# my-forecast.net
KiCad netlist of a schematic drawn in EAGLE
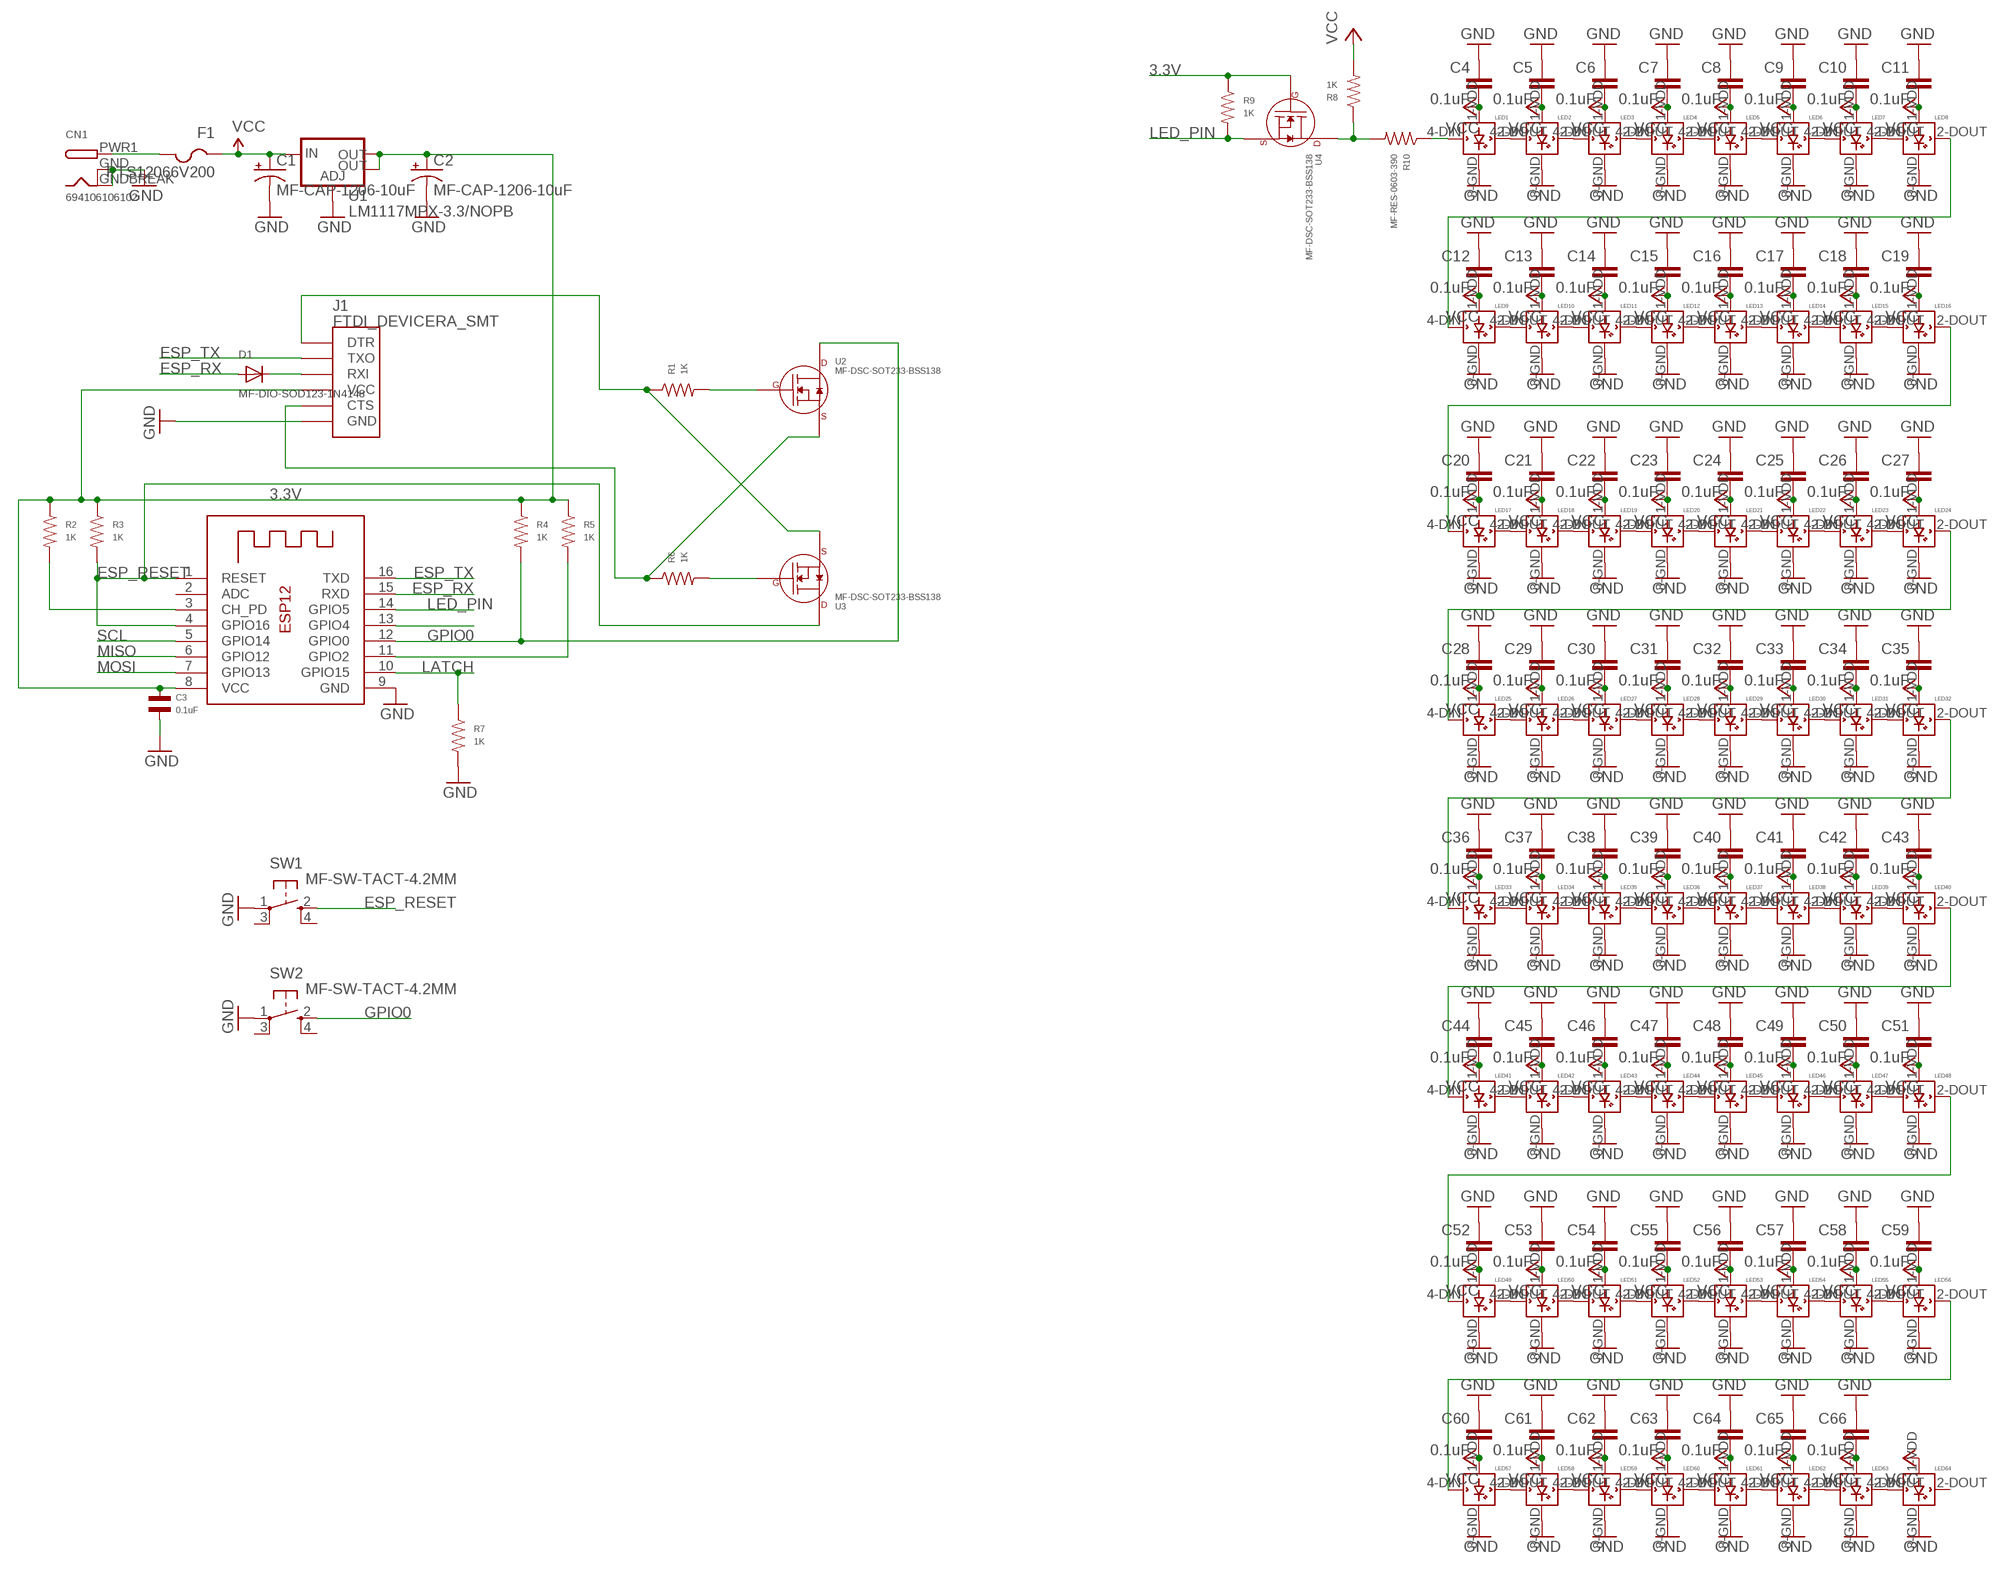
[diagram p0: schematic, sheet 1]

(export (version "E")
  (design (tool "Eeschema 10.0.6"))
  (components
    (comp (ref "C1")
      (value "MF-CAP-1206-10uF")
      (footprint "eagle-import:EIA3216")
      (libsource (lib "eagle-import") (part "CAP_POL1206"))
    )
    (comp (ref "C2")
      (value "MF-CAP-1206-10uF")
      (footprint "eagle-import:EIA3216")
      (libsource (lib "eagle-import") (part "CAP_POL1206"))
    )
    (comp (ref "C3")
      (value "0.1uF")
      (footprint "eagle-import:C0603")
      (libsource (lib "eagle-import") (part "CAPACITOR_NP_0603"))
    )
    (comp (ref "C4")
      (value "0.1uF")
      (footprint "eagle-import:0603-CAP")
      (libsource (lib "eagle-import") (part "CAP0603-CAP"))
    )
    (comp (ref "C5")
      (value "0.1uF")
      (footprint "eagle-import:0603-CAP")
      (libsource (lib "eagle-import") (part "CAP0603-CAP"))
    )
    (comp (ref "C6")
      (value "0.1uF")
      (footprint "eagle-import:0603-CAP")
      (libsource (lib "eagle-import") (part "CAP0603-CAP"))
    )
    (comp (ref "C7")
      (value "0.1uF")
      (footprint "eagle-import:0603-CAP")
      (libsource (lib "eagle-import") (part "CAP0603-CAP"))
    )
    (comp (ref "C8")
      (value "0.1uF")
      (footprint "eagle-import:0603-CAP")
      (libsource (lib "eagle-import") (part "CAP0603-CAP"))
    )
    (comp (ref "C9")
      (value "0.1uF")
      (footprint "eagle-import:0603-CAP")
      (libsource (lib "eagle-import") (part "CAP0603-CAP"))
    )
    (comp (ref "C10")
      (value "0.1uF")
      (footprint "eagle-import:0603-CAP")
      (libsource (lib "eagle-import") (part "CAP0603-CAP"))
    )
    (comp (ref "C11")
      (value "0.1uF")
      (footprint "eagle-import:0603-CAP")
      (libsource (lib "eagle-import") (part "CAP0603-CAP"))
    )
    (comp (ref "C12")
      (value "0.1uF")
      (footprint "eagle-import:0603-CAP")
      (libsource (lib "eagle-import") (part "CAP0603-CAP"))
    )
    (comp (ref "C13")
      (value "0.1uF")
      (footprint "eagle-import:0603-CAP")
      (libsource (lib "eagle-import") (part "CAP0603-CAP"))
    )
    (comp (ref "C14")
      (value "0.1uF")
      (footprint "eagle-import:0603-CAP")
      (libsource (lib "eagle-import") (part "CAP0603-CAP"))
    )
    (comp (ref "C15")
      (value "0.1uF")
      (footprint "eagle-import:0603-CAP")
      (libsource (lib "eagle-import") (part "CAP0603-CAP"))
    )
    (comp (ref "C16")
      (value "0.1uF")
      (footprint "eagle-import:0603-CAP")
      (libsource (lib "eagle-import") (part "CAP0603-CAP"))
    )
    (comp (ref "C17")
      (value "0.1uF")
      (footprint "eagle-import:0603-CAP")
      (libsource (lib "eagle-import") (part "CAP0603-CAP"))
    )
    (comp (ref "C18")
      (value "0.1uF")
      (footprint "eagle-import:0603-CAP")
      (libsource (lib "eagle-import") (part "CAP0603-CAP"))
    )
    (comp (ref "C19")
      (value "0.1uF")
      (footprint "eagle-import:0603-CAP")
      (libsource (lib "eagle-import") (part "CAP0603-CAP"))
    )
    (comp (ref "C20")
      (value "0.1uF")
      (footprint "eagle-import:0603-CAP")
      (libsource (lib "eagle-import") (part "CAP0603-CAP"))
    )
    (comp (ref "C21")
      (value "0.1uF")
      (footprint "eagle-import:0603-CAP")
      (libsource (lib "eagle-import") (part "CAP0603-CAP"))
    )
    (comp (ref "C22")
      (value "0.1uF")
      (footprint "eagle-import:0603-CAP")
      (libsource (lib "eagle-import") (part "CAP0603-CAP"))
    )
    (comp (ref "C23")
      (value "0.1uF")
      (footprint "eagle-import:0603-CAP")
      (libsource (lib "eagle-import") (part "CAP0603-CAP"))
    )
    (comp (ref "C24")
      (value "0.1uF")
      (footprint "eagle-import:0603-CAP")
      (libsource (lib "eagle-import") (part "CAP0603-CAP"))
    )
    (comp (ref "C25")
      (value "0.1uF")
      (footprint "eagle-import:0603-CAP")
      (libsource (lib "eagle-import") (part "CAP0603-CAP"))
    )
    (comp (ref "C26")
      (value "0.1uF")
      (footprint "eagle-import:0603-CAP")
      (libsource (lib "eagle-import") (part "CAP0603-CAP"))
    )
    (comp (ref "C27")
      (value "0.1uF")
      (footprint "eagle-import:0603-CAP")
      (libsource (lib "eagle-import") (part "CAP0603-CAP"))
    )
    (comp (ref "C28")
      (value "0.1uF")
      (footprint "eagle-import:0603-CAP")
      (libsource (lib "eagle-import") (part "CAP0603-CAP"))
    )
    (comp (ref "C29")
      (value "0.1uF")
      (footprint "eagle-import:0603-CAP")
      (libsource (lib "eagle-import") (part "CAP0603-CAP"))
    )
    (comp (ref "C30")
      (value "0.1uF")
      (footprint "eagle-import:0603-CAP")
      (libsource (lib "eagle-import") (part "CAP0603-CAP"))
    )
    (comp (ref "C31")
      (value "0.1uF")
      (footprint "eagle-import:0603-CAP")
      (libsource (lib "eagle-import") (part "CAP0603-CAP"))
    )
    (comp (ref "C32")
      (value "0.1uF")
      (footprint "eagle-import:0603-CAP")
      (libsource (lib "eagle-import") (part "CAP0603-CAP"))
    )
    (comp (ref "C33")
      (value "0.1uF")
      (footprint "eagle-import:0603-CAP")
      (libsource (lib "eagle-import") (part "CAP0603-CAP"))
    )
    (comp (ref "C34")
      (value "0.1uF")
      (footprint "eagle-import:0603-CAP")
      (libsource (lib "eagle-import") (part "CAP0603-CAP"))
    )
    (comp (ref "C35")
      (value "0.1uF")
      (footprint "eagle-import:0603-CAP")
      (libsource (lib "eagle-import") (part "CAP0603-CAP"))
    )
    (comp (ref "C36")
      (value "0.1uF")
      (footprint "eagle-import:0603-CAP")
      (libsource (lib "eagle-import") (part "CAP0603-CAP"))
    )
    (comp (ref "C37")
      (value "0.1uF")
      (footprint "eagle-import:0603-CAP")
      (libsource (lib "eagle-import") (part "CAP0603-CAP"))
    )
    (comp (ref "C38")
      (value "0.1uF")
      (footprint "eagle-import:0603-CAP")
      (libsource (lib "eagle-import") (part "CAP0603-CAP"))
    )
    (comp (ref "C39")
      (value "0.1uF")
      (footprint "eagle-import:0603-CAP")
      (libsource (lib "eagle-import") (part "CAP0603-CAP"))
    )
    (comp (ref "C40")
      (value "0.1uF")
      (footprint "eagle-import:0603-CAP")
      (libsource (lib "eagle-import") (part "CAP0603-CAP"))
    )
    (comp (ref "C41")
      (value "0.1uF")
      (footprint "eagle-import:0603-CAP")
      (libsource (lib "eagle-import") (part "CAP0603-CAP"))
    )
    (comp (ref "C42")
      (value "0.1uF")
      (footprint "eagle-import:0603-CAP")
      (libsource (lib "eagle-import") (part "CAP0603-CAP"))
    )
    (comp (ref "C43")
      (value "0.1uF")
      (footprint "eagle-import:0603-CAP")
      (libsource (lib "eagle-import") (part "CAP0603-CAP"))
    )
    (comp (ref "C44")
      (value "0.1uF")
      (footprint "eagle-import:0603-CAP")
      (libsource (lib "eagle-import") (part "CAP0603-CAP"))
    )
    (comp (ref "C45")
      (value "0.1uF")
      (footprint "eagle-import:0603-CAP")
      (libsource (lib "eagle-import") (part "CAP0603-CAP"))
    )
    (comp (ref "C46")
      (value "0.1uF")
      (footprint "eagle-import:0603-CAP")
      (libsource (lib "eagle-import") (part "CAP0603-CAP"))
    )
    (comp (ref "C47")
      (value "0.1uF")
      (footprint "eagle-import:0603-CAP")
      (libsource (lib "eagle-import") (part "CAP0603-CAP"))
    )
    (comp (ref "C48")
      (value "0.1uF")
      (footprint "eagle-import:0603-CAP")
      (libsource (lib "eagle-import") (part "CAP0603-CAP"))
    )
    (comp (ref "C49")
      (value "0.1uF")
      (footprint "eagle-import:0603-CAP")
      (libsource (lib "eagle-import") (part "CAP0603-CAP"))
    )
    (comp (ref "C50")
      (value "0.1uF")
      (footprint "eagle-import:0603-CAP")
      (libsource (lib "eagle-import") (part "CAP0603-CAP"))
    )
    (comp (ref "C51")
      (value "0.1uF")
      (footprint "eagle-import:0603-CAP")
      (libsource (lib "eagle-import") (part "CAP0603-CAP"))
    )
    (comp (ref "C52")
      (value "0.1uF")
      (footprint "eagle-import:0603-CAP")
      (libsource (lib "eagle-import") (part "CAP0603-CAP"))
    )
    (comp (ref "C53")
      (value "0.1uF")
      (footprint "eagle-import:0603-CAP")
      (libsource (lib "eagle-import") (part "CAP0603-CAP"))
    )
    (comp (ref "C54")
      (value "0.1uF")
      (footprint "eagle-import:0603-CAP")
      (libsource (lib "eagle-import") (part "CAP0603-CAP"))
    )
    (comp (ref "C55")
      (value "0.1uF")
      (footprint "eagle-import:0603-CAP")
      (libsource (lib "eagle-import") (part "CAP0603-CAP"))
    )
    (comp (ref "C56")
      (value "0.1uF")
      (footprint "eagle-import:0603-CAP")
      (libsource (lib "eagle-import") (part "CAP0603-CAP"))
    )
    (comp (ref "C57")
      (value "0.1uF")
      (footprint "eagle-import:0603-CAP")
      (libsource (lib "eagle-import") (part "CAP0603-CAP"))
    )
    (comp (ref "C58")
      (value "0.1uF")
      (footprint "eagle-import:0603-CAP")
      (libsource (lib "eagle-import") (part "CAP0603-CAP"))
    )
    (comp (ref "C59")
      (value "0.1uF")
      (footprint "eagle-import:0603-CAP")
      (libsource (lib "eagle-import") (part "CAP0603-CAP"))
    )
    (comp (ref "C60")
      (value "0.1uF")
      (footprint "eagle-import:0603-CAP")
      (libsource (lib "eagle-import") (part "CAP0603-CAP"))
    )
    (comp (ref "C61")
      (value "0.1uF")
      (footprint "eagle-import:0603-CAP")
      (libsource (lib "eagle-import") (part "CAP0603-CAP"))
    )
    (comp (ref "C62")
      (value "0.1uF")
      (footprint "eagle-import:0603-CAP")
      (libsource (lib "eagle-import") (part "CAP0603-CAP"))
    )
    (comp (ref "C63")
      (value "0.1uF")
      (footprint "eagle-import:0603-CAP")
      (libsource (lib "eagle-import") (part "CAP0603-CAP"))
    )
    (comp (ref "C64")
      (value "0.1uF")
      (footprint "eagle-import:0603-CAP")
      (libsource (lib "eagle-import") (part "CAP0603-CAP"))
    )
    (comp (ref "C65")
      (value "0.1uF")
      (footprint "eagle-import:0603-CAP")
      (libsource (lib "eagle-import") (part "CAP0603-CAP"))
    )
    (comp (ref "C66")
      (value "0.1uF")
      (footprint "eagle-import:0603-CAP")
      (libsource (lib "eagle-import") (part "CAP0603-CAP"))
    )
    (comp (ref "CN1")
      (value "694106106102")
      (footprint "eagle-import:DCJACK_2MM_SMT")
      (libsource (lib "eagle-import") (part "DCBARRELSMT"))
    )
    (comp (ref "D1")
      (value "MF-DIO-SOD123-1N4148")
      (footprint "eagle-import:SOD-123")
      (libsource (lib "eagle-import") (part "DIODESOD-123"))
    )
    (comp (ref "F1")
      (value "PTS12066V200")
      (footprint "eagle-import:R1206")
      (libsource (lib "eagle-import") (part "PTCFUSE-1206"))
    )
    (comp (ref "J1")
      (value "FTDI_DEVICERA_SMT")
      (footprint "eagle-import:FTDI_DEVICE_RA_SMT")
      (libsource (lib "eagle-import") (part "FTDI_DEVICERA_SMT"))
    )
    (comp (ref "LED1")
      (value "WS2812B5050")
      (footprint "eagle-import:WS2812B")
      (libsource (lib "eagle-import") (part "WS2812B5050"))
    )
    (comp (ref "LED2")
      (value "WS2812B5050")
      (footprint "eagle-import:WS2812B")
      (libsource (lib "eagle-import") (part "WS2812B5050"))
    )
    (comp (ref "LED3")
      (value "WS2812B5050")
      (footprint "eagle-import:WS2812B")
      (libsource (lib "eagle-import") (part "WS2812B5050"))
    )
    (comp (ref "LED4")
      (value "WS2812B5050")
      (footprint "eagle-import:WS2812B")
      (libsource (lib "eagle-import") (part "WS2812B5050"))
    )
    (comp (ref "LED5")
      (value "WS2812B5050")
      (footprint "eagle-import:WS2812B")
      (libsource (lib "eagle-import") (part "WS2812B5050"))
    )
    (comp (ref "LED6")
      (value "WS2812B5050")
      (footprint "eagle-import:WS2812B")
      (libsource (lib "eagle-import") (part "WS2812B5050"))
    )
    (comp (ref "LED7")
      (value "WS2812B5050")
      (footprint "eagle-import:WS2812B")
      (libsource (lib "eagle-import") (part "WS2812B5050"))
    )
    (comp (ref "LED8")
      (value "WS2812B5050")
      (footprint "eagle-import:WS2812B")
      (libsource (lib "eagle-import") (part "WS2812B5050"))
    )
    (comp (ref "LED9")
      (value "WS2812B5050")
      (footprint "eagle-import:WS2812B")
      (libsource (lib "eagle-import") (part "WS2812B5050"))
    )
    (comp (ref "LED10")
      (value "WS2812B5050")
      (footprint "eagle-import:WS2812B")
      (libsource (lib "eagle-import") (part "WS2812B5050"))
    )
    (comp (ref "LED11")
      (value "WS2812B5050")
      (footprint "eagle-import:WS2812B")
      (libsource (lib "eagle-import") (part "WS2812B5050"))
    )
    (comp (ref "LED12")
      (value "WS2812B5050")
      (footprint "eagle-import:WS2812B")
      (libsource (lib "eagle-import") (part "WS2812B5050"))
    )
    (comp (ref "LED13")
      (value "WS2812B5050")
      (footprint "eagle-import:WS2812B")
      (libsource (lib "eagle-import") (part "WS2812B5050"))
    )
    (comp (ref "LED14")
      (value "WS2812B5050")
      (footprint "eagle-import:WS2812B")
      (libsource (lib "eagle-import") (part "WS2812B5050"))
    )
    (comp (ref "LED15")
      (value "WS2812B5050")
      (footprint "eagle-import:WS2812B")
      (libsource (lib "eagle-import") (part "WS2812B5050"))
    )
    (comp (ref "LED16")
      (value "WS2812B5050")
      (footprint "eagle-import:WS2812B")
      (libsource (lib "eagle-import") (part "WS2812B5050"))
    )
    (comp (ref "LED17")
      (value "WS2812B5050")
      (footprint "eagle-import:WS2812B")
      (libsource (lib "eagle-import") (part "WS2812B5050"))
    )
    (comp (ref "LED18")
      (value "WS2812B5050")
      (footprint "eagle-import:WS2812B")
      (libsource (lib "eagle-import") (part "WS2812B5050"))
    )
    (comp (ref "LED19")
      (value "WS2812B5050")
      (footprint "eagle-import:WS2812B")
      (libsource (lib "eagle-import") (part "WS2812B5050"))
    )
    (comp (ref "LED20")
      (value "WS2812B5050")
      (footprint "eagle-import:WS2812B")
      (libsource (lib "eagle-import") (part "WS2812B5050"))
    )
    (comp (ref "LED21")
      (value "WS2812B5050")
      (footprint "eagle-import:WS2812B")
      (libsource (lib "eagle-import") (part "WS2812B5050"))
    )
    (comp (ref "LED22")
      (value "WS2812B5050")
      (footprint "eagle-import:WS2812B")
      (libsource (lib "eagle-import") (part "WS2812B5050"))
    )
    (comp (ref "LED23")
      (value "WS2812B5050")
      (footprint "eagle-import:WS2812B")
      (libsource (lib "eagle-import") (part "WS2812B5050"))
    )
    (comp (ref "LED24")
      (value "WS2812B5050")
      (footprint "eagle-import:WS2812B")
      (libsource (lib "eagle-import") (part "WS2812B5050"))
    )
    (comp (ref "LED25")
      (value "WS2812B5050")
      (footprint "eagle-import:WS2812B")
      (libsource (lib "eagle-import") (part "WS2812B5050"))
    )
    (comp (ref "LED26")
      (value "WS2812B5050")
      (footprint "eagle-import:WS2812B")
      (libsource (lib "eagle-import") (part "WS2812B5050"))
    )
    (comp (ref "LED27")
      (value "WS2812B5050")
      (footprint "eagle-import:WS2812B")
      (libsource (lib "eagle-import") (part "WS2812B5050"))
    )
    (comp (ref "LED28")
      (value "WS2812B5050")
      (footprint "eagle-import:WS2812B")
      (libsource (lib "eagle-import") (part "WS2812B5050"))
    )
    (comp (ref "LED29")
      (value "WS2812B5050")
      (footprint "eagle-import:WS2812B")
      (libsource (lib "eagle-import") (part "WS2812B5050"))
    )
    (comp (ref "LED30")
      (value "WS2812B5050")
      (footprint "eagle-import:WS2812B")
      (libsource (lib "eagle-import") (part "WS2812B5050"))
    )
    (comp (ref "LED31")
      (value "WS2812B5050")
      (footprint "eagle-import:WS2812B")
      (libsource (lib "eagle-import") (part "WS2812B5050"))
    )
    (comp (ref "LED32")
      (value "WS2812B5050")
      (footprint "eagle-import:WS2812B")
      (libsource (lib "eagle-import") (part "WS2812B5050"))
    )
    (comp (ref "LED33")
      (value "WS2812B5050")
      (footprint "eagle-import:WS2812B")
      (libsource (lib "eagle-import") (part "WS2812B5050"))
    )
    (comp (ref "LED34")
      (value "WS2812B5050")
      (footprint "eagle-import:WS2812B")
      (libsource (lib "eagle-import") (part "WS2812B5050"))
    )
    (comp (ref "LED35")
      (value "WS2812B5050")
      (footprint "eagle-import:WS2812B")
      (libsource (lib "eagle-import") (part "WS2812B5050"))
    )
    (comp (ref "LED36")
      (value "WS2812B5050")
      (footprint "eagle-import:WS2812B")
      (libsource (lib "eagle-import") (part "WS2812B5050"))
    )
    (comp (ref "LED37")
      (value "WS2812B5050")
      (footprint "eagle-import:WS2812B")
      (libsource (lib "eagle-import") (part "WS2812B5050"))
    )
    (comp (ref "LED38")
      (value "WS2812B5050")
      (footprint "eagle-import:WS2812B")
      (libsource (lib "eagle-import") (part "WS2812B5050"))
    )
    (comp (ref "LED39")
      (value "WS2812B5050")
      (footprint "eagle-import:WS2812B")
      (libsource (lib "eagle-import") (part "WS2812B5050"))
    )
    (comp (ref "LED40")
      (value "WS2812B5050")
      (footprint "eagle-import:WS2812B")
      (libsource (lib "eagle-import") (part "WS2812B5050"))
    )
    (comp (ref "LED41")
      (value "WS2812B5050")
      (footprint "eagle-import:WS2812B")
      (libsource (lib "eagle-import") (part "WS2812B5050"))
    )
    (comp (ref "LED42")
      (value "WS2812B5050")
      (footprint "eagle-import:WS2812B")
      (libsource (lib "eagle-import") (part "WS2812B5050"))
    )
    (comp (ref "LED43")
      (value "WS2812B5050")
      (footprint "eagle-import:WS2812B")
      (libsource (lib "eagle-import") (part "WS2812B5050"))
    )
    (comp (ref "LED44")
      (value "WS2812B5050")
      (footprint "eagle-import:WS2812B")
      (libsource (lib "eagle-import") (part "WS2812B5050"))
    )
    (comp (ref "LED45")
      (value "WS2812B5050")
      (footprint "eagle-import:WS2812B")
      (libsource (lib "eagle-import") (part "WS2812B5050"))
    )
    (comp (ref "LED46")
      (value "WS2812B5050")
      (footprint "eagle-import:WS2812B")
      (libsource (lib "eagle-import") (part "WS2812B5050"))
    )
    (comp (ref "LED47")
      (value "WS2812B5050")
      (footprint "eagle-import:WS2812B")
      (libsource (lib "eagle-import") (part "WS2812B5050"))
    )
    (comp (ref "LED48")
      (value "WS2812B5050")
      (footprint "eagle-import:WS2812B")
      (libsource (lib "eagle-import") (part "WS2812B5050"))
    )
    (comp (ref "LED49")
      (value "WS2812B5050")
      (footprint "eagle-import:WS2812B")
      (libsource (lib "eagle-import") (part "WS2812B5050"))
    )
    (comp (ref "LED50")
      (value "WS2812B5050")
      (footprint "eagle-import:WS2812B")
      (libsource (lib "eagle-import") (part "WS2812B5050"))
    )
    (comp (ref "LED51")
      (value "WS2812B5050")
      (footprint "eagle-import:WS2812B")
      (libsource (lib "eagle-import") (part "WS2812B5050"))
    )
    (comp (ref "LED52")
      (value "WS2812B5050")
      (footprint "eagle-import:WS2812B")
      (libsource (lib "eagle-import") (part "WS2812B5050"))
    )
    (comp (ref "LED53")
      (value "WS2812B5050")
      (footprint "eagle-import:WS2812B")
      (libsource (lib "eagle-import") (part "WS2812B5050"))
    )
    (comp (ref "LED54")
      (value "WS2812B5050")
      (footprint "eagle-import:WS2812B")
      (libsource (lib "eagle-import") (part "WS2812B5050"))
    )
    (comp (ref "LED55")
      (value "WS2812B5050")
      (footprint "eagle-import:WS2812B")
      (libsource (lib "eagle-import") (part "WS2812B5050"))
    )
    (comp (ref "LED56")
      (value "WS2812B5050")
      (footprint "eagle-import:WS2812B")
      (libsource (lib "eagle-import") (part "WS2812B5050"))
    )
    (comp (ref "LED57")
      (value "WS2812B5050")
      (footprint "eagle-import:WS2812B")
      (libsource (lib "eagle-import") (part "WS2812B5050"))
    )
    (comp (ref "LED58")
      (value "WS2812B5050")
      (footprint "eagle-import:WS2812B")
      (libsource (lib "eagle-import") (part "WS2812B5050"))
    )
    (comp (ref "LED59")
      (value "WS2812B5050")
      (footprint "eagle-import:WS2812B")
      (libsource (lib "eagle-import") (part "WS2812B5050"))
    )
    (comp (ref "LED60")
      (value "WS2812B5050")
      (footprint "eagle-import:WS2812B")
      (libsource (lib "eagle-import") (part "WS2812B5050"))
    )
    (comp (ref "LED61")
      (value "WS2812B5050")
      (footprint "eagle-import:WS2812B")
      (libsource (lib "eagle-import") (part "WS2812B5050"))
    )
    (comp (ref "LED62")
      (value "WS2812B5050")
      (footprint "eagle-import:WS2812B")
      (libsource (lib "eagle-import") (part "WS2812B5050"))
    )
    (comp (ref "LED63")
      (value "WS2812B5050")
      (footprint "eagle-import:WS2812B")
      (libsource (lib "eagle-import") (part "WS2812B5050"))
    )
    (comp (ref "LED64")
      (value "WS2812B5050")
      (footprint "eagle-import:WS2812B")
      (libsource (lib "eagle-import") (part "WS2812B5050"))
    )
    (comp (ref "R1")
      (value "1K")
      (footprint "eagle-import:R0603")
      (libsource (lib "eagle-import") (part "RESISTOR_0603"))
    )
    (comp (ref "R2")
      (value "1K")
      (footprint "eagle-import:R0603")
      (libsource (lib "eagle-import") (part "RESISTOR_0603"))
    )
    (comp (ref "R3")
      (value "1K")
      (footprint "eagle-import:R0603")
      (libsource (lib "eagle-import") (part "RESISTOR_0603"))
    )
    (comp (ref "R4")
      (value "1K")
      (footprint "eagle-import:R0603")
      (libsource (lib "eagle-import") (part "RESISTOR_0603"))
    )
    (comp (ref "R5")
      (value "1K")
      (footprint "eagle-import:R0603")
      (libsource (lib "eagle-import") (part "RESISTOR_0603"))
    )
    (comp (ref "R6")
      (value "1K")
      (footprint "eagle-import:R0603")
      (libsource (lib "eagle-import") (part "RESISTOR_0603"))
    )
    (comp (ref "R7")
      (value "1K")
      (footprint "eagle-import:R0603")
      (libsource (lib "eagle-import") (part "RESISTOR_0603"))
    )
    (comp (ref "R8")
      (value "1K")
      (footprint "eagle-import:R0603")
      (libsource (lib "eagle-import") (part "RESISTOR_0603"))
    )
    (comp (ref "R9")
      (value "1K")
      (footprint "eagle-import:R0603")
      (libsource (lib "eagle-import") (part "RESISTOR_0603"))
    )
    (comp (ref "R10")
      (value "MF-RES-0603-390")
      (footprint "eagle-import:R0603")
      (libsource (lib "eagle-import") (part "RESISTOR_0603"))
    )
    (comp (ref "SW1")
      (value "MF-SW-TACT-4.2MM")
      (footprint "eagle-import:KMR2")
      (libsource (lib "eagle-import") (part "SPST_TACT-KMR2"))
    )
    (comp (ref "SW2")
      (value "MF-SW-TACT-4.2MM")
      (footprint "eagle-import:KMR2")
      (libsource (lib "eagle-import") (part "SPST_TACT-KMR2"))
    )
    (comp (ref "U1")
      (value "LM1117MPX-3.3/NOPB")
      (footprint "eagle-import:SOT223")
      (libsource (lib "eagle-import") (part "V_REG_LM1117SOT223"))
    )
    (comp (ref "U2")
      (value "MF-DSC-SOT233-BSS138")
      (footprint "eagle-import:SOT-23-3")
      (fields (field (name "HOUSEPART") "YES"))
      (libsource (lib "eagle-import") (part "N-CHANNEL_FET_SOT-23-3_BSS138"))
    )
    (comp (ref "U3")
      (value "MF-DSC-SOT233-BSS138")
      (footprint "eagle-import:SOT-23-3")
      (fields (field (name "HOUSEPART") "YES"))
      (libsource (lib "eagle-import") (part "N-CHANNEL_FET_SOT-23-3_BSS138"))
    )
    (comp (ref "U4")
      (value "MF-DSC-SOT233-BSS138")
      (footprint "eagle-import:SOT-23-3")
      (fields (field (name "HOUSEPART") "YES"))
      (libsource (lib "eagle-import") (part "N-CHANNEL_FET_SOT-23-3_BSS138"))
    )
    (comp (ref "X1")
      (value "ESP-12")
      (footprint "eagle-import:ESP-12")
      (libsource (lib "eagle-import") (part "ESP-12"))
    )
  )
  (nets
    (net (code "1") (name "/3.3V") (class "Default")
      (node (ref "C2") (pin "A") (pinfunction "+_A") (pintype "passive"))
      (node (ref "C3") (pin "P$1") (pinfunction "P$1_P$1") (pintype "passive"))
      (node (ref "J1") (pin "4") (pinfunction "VCC_4") (pintype "bidirectional"))
      (node (ref "R2") (pin "P$1") (pinfunction "P$1_P$1") (pintype "passive"))
      (node (ref "R3") (pin "P$1") (pinfunction "P$1_P$1") (pintype "passive"))
      (node (ref "R4") (pin "P$1") (pinfunction "P$1_P$1") (pintype "passive"))
      (node (ref "R5") (pin "P$1") (pinfunction "P$1_P$1") (pintype "passive"))
      (node (ref "R9") (pin "P$1") (pinfunction "P$1_P$1") (pintype "passive"))
      (node (ref "U1") (pin "2") (pinfunction "OUT_2") (pintype "output"))
      (node (ref "U1") (pin "4") (pinfunction "OUT_4") (pintype "output"))
      (node (ref "U4") (pin "P$1") (pinfunction "GATE_P$1") (pintype "bidirectional"))
      (node (ref "X1") (pin "8") (pinfunction "VCC_8") (pintype "power_in"))
    )
    (net (code "2") (name "/ESP_RESET") (class "Default")
      (node (ref "R3") (pin "P$2") (pinfunction "P$2_P$2") (pintype "passive"))
      (node (ref "SW1") (pin "2") (pinfunction "S_2") (pintype "passive"))
      (node (ref "U3") (pin "P$3") (pinfunction "DRAIN_P$3") (pintype "bidirectional"))
      (node (ref "X1") (pin "1") (pinfunction "RESET_1") (pintype "input"))
      (node (ref "X1") (pin "4") (pinfunction "GPIO16_4") (pintype "bidirectional"))
    )
    (net (code "3") (name "/ESP_RX") (class "Default")
      (node (ref "D1") (pin "A") (pinfunction "A_A") (pintype "passive"))
      (node (ref "X1") (pin "15") (pinfunction "RXD_15") (pintype "input"))
    )
    (net (code "4") (name "/ESP_TX") (class "Default")
      (node (ref "J1") (pin "2") (pinfunction "TXO_2") (pintype "bidirectional"))
      (node (ref "X1") (pin "16") (pinfunction "TXD_16") (pintype "output"))
    )
    (net (code "5") (name "/GPIO0") (class "Default")
      (node (ref "R4") (pin "P$2") (pinfunction "P$2_P$2") (pintype "passive"))
      (node (ref "SW2") (pin "2") (pinfunction "S_2") (pintype "passive"))
      (node (ref "U2") (pin "P$3") (pinfunction "DRAIN_P$3") (pintype "bidirectional"))
      (node (ref "X1") (pin "12") (pinfunction "GPIO0_12") (pintype "bidirectional"))
    )
    (net (code "6") (name "/LATCH") (class "Default")
      (node (ref "R7") (pin "P$1") (pinfunction "P$1_P$1") (pintype "passive"))
      (node (ref "X1") (pin "10") (pinfunction "GPIO15_10") (pintype "bidirectional"))
    )
    (net (code "7") (name "/LED_PIN") (class "Default")
      (node (ref "R9") (pin "P$2") (pinfunction "P$2_P$2") (pintype "passive"))
      (node (ref "U4") (pin "P$2") (pinfunction "SOURCE_P$2") (pintype "bidirectional"))
      (node (ref "X1") (pin "14") (pinfunction "GPIO5_14") (pintype "bidirectional"))
    )
    (net (code "8") (name "/MISO") (class "Default")
      (node (ref "X1") (pin "6") (pinfunction "GPIO12_6") (pintype "bidirectional"))
    )
    (net (code "9") (name "/MOSI") (class "Default")
      (node (ref "X1") (pin "7") (pinfunction "GPIO13_7") (pintype "bidirectional"))
    )
    (net (code "10") (name "/SCL") (class "Default")
      (node (ref "X1") (pin "5") (pinfunction "GPIO14_5") (pintype "bidirectional"))
    )
    (net (code "11") (name "GND") (class "Default")
      (node (ref "C1") (pin "C") (pinfunction "-_C") (pintype "passive"))
      (node (ref "C10") (pin "1") (pinfunction "1_1") (pintype "passive"))
      (node (ref "C11") (pin "1") (pinfunction "1_1") (pintype "passive"))
      (node (ref "C12") (pin "1") (pinfunction "1_1") (pintype "passive"))
      (node (ref "C13") (pin "1") (pinfunction "1_1") (pintype "passive"))
      (node (ref "C14") (pin "1") (pinfunction "1_1") (pintype "passive"))
      (node (ref "C15") (pin "1") (pinfunction "1_1") (pintype "passive"))
      (node (ref "C16") (pin "1") (pinfunction "1_1") (pintype "passive"))
      (node (ref "C17") (pin "1") (pinfunction "1_1") (pintype "passive"))
      (node (ref "C18") (pin "1") (pinfunction "1_1") (pintype "passive"))
      (node (ref "C19") (pin "1") (pinfunction "1_1") (pintype "passive"))
      (node (ref "C2") (pin "C") (pinfunction "-_C") (pintype "passive"))
      (node (ref "C20") (pin "1") (pinfunction "1_1") (pintype "passive"))
      (node (ref "C21") (pin "1") (pinfunction "1_1") (pintype "passive"))
      (node (ref "C22") (pin "1") (pinfunction "1_1") (pintype "passive"))
      (node (ref "C23") (pin "1") (pinfunction "1_1") (pintype "passive"))
      (node (ref "C24") (pin "1") (pinfunction "1_1") (pintype "passive"))
      (node (ref "C25") (pin "1") (pinfunction "1_1") (pintype "passive"))
      (node (ref "C26") (pin "1") (pinfunction "1_1") (pintype "passive"))
      (node (ref "C27") (pin "1") (pinfunction "1_1") (pintype "passive"))
      (node (ref "C28") (pin "1") (pinfunction "1_1") (pintype "passive"))
      (node (ref "C29") (pin "1") (pinfunction "1_1") (pintype "passive"))
      (node (ref "C3") (pin "P$2") (pinfunction "P$2_P$2") (pintype "passive"))
      (node (ref "C30") (pin "1") (pinfunction "1_1") (pintype "passive"))
      (node (ref "C31") (pin "1") (pinfunction "1_1") (pintype "passive"))
      (node (ref "C32") (pin "1") (pinfunction "1_1") (pintype "passive"))
      (node (ref "C33") (pin "1") (pinfunction "1_1") (pintype "passive"))
      (node (ref "C34") (pin "1") (pinfunction "1_1") (pintype "passive"))
      (node (ref "C35") (pin "1") (pinfunction "1_1") (pintype "passive"))
      (node (ref "C36") (pin "1") (pinfunction "1_1") (pintype "passive"))
      (node (ref "C37") (pin "1") (pinfunction "1_1") (pintype "passive"))
      (node (ref "C38") (pin "1") (pinfunction "1_1") (pintype "passive"))
      (node (ref "C39") (pin "1") (pinfunction "1_1") (pintype "passive"))
      (node (ref "C4") (pin "1") (pinfunction "1_1") (pintype "passive"))
      (node (ref "C40") (pin "1") (pinfunction "1_1") (pintype "passive"))
      (node (ref "C41") (pin "1") (pinfunction "1_1") (pintype "passive"))
      (node (ref "C42") (pin "1") (pinfunction "1_1") (pintype "passive"))
      (node (ref "C43") (pin "1") (pinfunction "1_1") (pintype "passive"))
      (node (ref "C44") (pin "1") (pinfunction "1_1") (pintype "passive"))
      (node (ref "C45") (pin "1") (pinfunction "1_1") (pintype "passive"))
      (node (ref "C46") (pin "1") (pinfunction "1_1") (pintype "passive"))
      (node (ref "C47") (pin "1") (pinfunction "1_1") (pintype "passive"))
      (node (ref "C48") (pin "1") (pinfunction "1_1") (pintype "passive"))
      (node (ref "C49") (pin "1") (pinfunction "1_1") (pintype "passive"))
      (node (ref "C5") (pin "1") (pinfunction "1_1") (pintype "passive"))
      (node (ref "C50") (pin "1") (pinfunction "1_1") (pintype "passive"))
      (node (ref "C51") (pin "1") (pinfunction "1_1") (pintype "passive"))
      (node (ref "C52") (pin "1") (pinfunction "1_1") (pintype "passive"))
      (node (ref "C53") (pin "1") (pinfunction "1_1") (pintype "passive"))
      (node (ref "C54") (pin "1") (pinfunction "1_1") (pintype "passive"))
      (node (ref "C55") (pin "1") (pinfunction "1_1") (pintype "passive"))
      (node (ref "C56") (pin "1") (pinfunction "1_1") (pintype "passive"))
      (node (ref "C57") (pin "1") (pinfunction "1_1") (pintype "passive"))
      (node (ref "C58") (pin "1") (pinfunction "1_1") (pintype "passive"))
      (node (ref "C59") (pin "1") (pinfunction "1_1") (pintype "passive"))
      (node (ref "C6") (pin "1") (pinfunction "1_1") (pintype "passive"))
      (node (ref "C60") (pin "1") (pinfunction "1_1") (pintype "passive"))
      (node (ref "C61") (pin "1") (pinfunction "1_1") (pintype "passive"))
      (node (ref "C62") (pin "1") (pinfunction "1_1") (pintype "passive"))
      (node (ref "C63") (pin "1") (pinfunction "1_1") (pintype "passive"))
      (node (ref "C64") (pin "1") (pinfunction "1_1") (pintype "passive"))
      (node (ref "C65") (pin "1") (pinfunction "1_1") (pintype "passive"))
      (node (ref "C66") (pin "1") (pinfunction "1_1") (pintype "passive"))
      (node (ref "C7") (pin "1") (pinfunction "1_1") (pintype "passive"))
      (node (ref "C8") (pin "1") (pinfunction "1_1") (pintype "passive"))
      (node (ref "C9") (pin "1") (pinfunction "1_1") (pintype "passive"))
      (node (ref "CN1") (pin "GND") (pinfunction "GNDBREAK_GND") (pintype "power_in"))
      (node (ref "CN1") (pin "GNDBREAK") (pinfunction "GND_GNDBREAK") (pintype "power_in"))
      (node (ref "J1") (pin "6") (pinfunction "GND_6") (pintype "bidirectional"))
      (node (ref "LED1") (pin "3-GND") (pinfunction "GND_3-GND") (pintype "bidirectional"))
      (node (ref "LED10") (pin "3-GND") (pinfunction "GND_3-GND") (pintype "bidirectional"))
      (node (ref "LED11") (pin "3-GND") (pinfunction "GND_3-GND") (pintype "bidirectional"))
      (node (ref "LED12") (pin "3-GND") (pinfunction "GND_3-GND") (pintype "bidirectional"))
      (node (ref "LED13") (pin "3-GND") (pinfunction "GND_3-GND") (pintype "bidirectional"))
      (node (ref "LED14") (pin "3-GND") (pinfunction "GND_3-GND") (pintype "bidirectional"))
      (node (ref "LED15") (pin "3-GND") (pinfunction "GND_3-GND") (pintype "bidirectional"))
      (node (ref "LED16") (pin "3-GND") (pinfunction "GND_3-GND") (pintype "bidirectional"))
      (node (ref "LED17") (pin "3-GND") (pinfunction "GND_3-GND") (pintype "bidirectional"))
      (node (ref "LED18") (pin "3-GND") (pinfunction "GND_3-GND") (pintype "bidirectional"))
      (node (ref "LED19") (pin "3-GND") (pinfunction "GND_3-GND") (pintype "bidirectional"))
      (node (ref "LED2") (pin "3-GND") (pinfunction "GND_3-GND") (pintype "bidirectional"))
      (node (ref "LED20") (pin "3-GND") (pinfunction "GND_3-GND") (pintype "bidirectional"))
      (node (ref "LED21") (pin "3-GND") (pinfunction "GND_3-GND") (pintype "bidirectional"))
      (node (ref "LED22") (pin "3-GND") (pinfunction "GND_3-GND") (pintype "bidirectional"))
      (node (ref "LED23") (pin "3-GND") (pinfunction "GND_3-GND") (pintype "bidirectional"))
      (node (ref "LED24") (pin "3-GND") (pinfunction "GND_3-GND") (pintype "bidirectional"))
      (node (ref "LED25") (pin "3-GND") (pinfunction "GND_3-GND") (pintype "bidirectional"))
      (node (ref "LED26") (pin "3-GND") (pinfunction "GND_3-GND") (pintype "bidirectional"))
      (node (ref "LED27") (pin "3-GND") (pinfunction "GND_3-GND") (pintype "bidirectional"))
      (node (ref "LED28") (pin "3-GND") (pinfunction "GND_3-GND") (pintype "bidirectional"))
      (node (ref "LED29") (pin "3-GND") (pinfunction "GND_3-GND") (pintype "bidirectional"))
      (node (ref "LED3") (pin "3-GND") (pinfunction "GND_3-GND") (pintype "bidirectional"))
      (node (ref "LED30") (pin "3-GND") (pinfunction "GND_3-GND") (pintype "bidirectional"))
      (node (ref "LED31") (pin "3-GND") (pinfunction "GND_3-GND") (pintype "bidirectional"))
      (node (ref "LED32") (pin "3-GND") (pinfunction "GND_3-GND") (pintype "bidirectional"))
      (node (ref "LED33") (pin "3-GND") (pinfunction "GND_3-GND") (pintype "bidirectional"))
      (node (ref "LED34") (pin "3-GND") (pinfunction "GND_3-GND") (pintype "bidirectional"))
      (node (ref "LED35") (pin "3-GND") (pinfunction "GND_3-GND") (pintype "bidirectional"))
      (node (ref "LED36") (pin "3-GND") (pinfunction "GND_3-GND") (pintype "bidirectional"))
      (node (ref "LED37") (pin "3-GND") (pinfunction "GND_3-GND") (pintype "bidirectional"))
      (node (ref "LED38") (pin "3-GND") (pinfunction "GND_3-GND") (pintype "bidirectional"))
      (node (ref "LED39") (pin "3-GND") (pinfunction "GND_3-GND") (pintype "bidirectional"))
      (node (ref "LED4") (pin "3-GND") (pinfunction "GND_3-GND") (pintype "bidirectional"))
      (node (ref "LED40") (pin "3-GND") (pinfunction "GND_3-GND") (pintype "bidirectional"))
      (node (ref "LED41") (pin "3-GND") (pinfunction "GND_3-GND") (pintype "bidirectional"))
      (node (ref "LED42") (pin "3-GND") (pinfunction "GND_3-GND") (pintype "bidirectional"))
      (node (ref "LED43") (pin "3-GND") (pinfunction "GND_3-GND") (pintype "bidirectional"))
      (node (ref "LED44") (pin "3-GND") (pinfunction "GND_3-GND") (pintype "bidirectional"))
      (node (ref "LED45") (pin "3-GND") (pinfunction "GND_3-GND") (pintype "bidirectional"))
      (node (ref "LED46") (pin "3-GND") (pinfunction "GND_3-GND") (pintype "bidirectional"))
      (node (ref "LED47") (pin "3-GND") (pinfunction "GND_3-GND") (pintype "bidirectional"))
      (node (ref "LED48") (pin "3-GND") (pinfunction "GND_3-GND") (pintype "bidirectional"))
      (node (ref "LED49") (pin "3-GND") (pinfunction "GND_3-GND") (pintype "bidirectional"))
      (node (ref "LED5") (pin "3-GND") (pinfunction "GND_3-GND") (pintype "bidirectional"))
      (node (ref "LED50") (pin "3-GND") (pinfunction "GND_3-GND") (pintype "bidirectional"))
      (node (ref "LED51") (pin "3-GND") (pinfunction "GND_3-GND") (pintype "bidirectional"))
      (node (ref "LED52") (pin "3-GND") (pinfunction "GND_3-GND") (pintype "bidirectional"))
      (node (ref "LED53") (pin "3-GND") (pinfunction "GND_3-GND") (pintype "bidirectional"))
      (node (ref "LED54") (pin "3-GND") (pinfunction "GND_3-GND") (pintype "bidirectional"))
      (node (ref "LED55") (pin "3-GND") (pinfunction "GND_3-GND") (pintype "bidirectional"))
      (node (ref "LED56") (pin "3-GND") (pinfunction "GND_3-GND") (pintype "bidirectional"))
      (node (ref "LED57") (pin "3-GND") (pinfunction "GND_3-GND") (pintype "bidirectional"))
      (node (ref "LED58") (pin "3-GND") (pinfunction "GND_3-GND") (pintype "bidirectional"))
      (node (ref "LED59") (pin "3-GND") (pinfunction "GND_3-GND") (pintype "bidirectional"))
      (node (ref "LED6") (pin "3-GND") (pinfunction "GND_3-GND") (pintype "bidirectional"))
      (node (ref "LED60") (pin "3-GND") (pinfunction "GND_3-GND") (pintype "bidirectional"))
      (node (ref "LED61") (pin "3-GND") (pinfunction "GND_3-GND") (pintype "bidirectional"))
      (node (ref "LED62") (pin "3-GND") (pinfunction "GND_3-GND") (pintype "bidirectional"))
      (node (ref "LED63") (pin "3-GND") (pinfunction "GND_3-GND") (pintype "bidirectional"))
      (node (ref "LED64") (pin "3-GND") (pinfunction "GND_3-GND") (pintype "bidirectional"))
      (node (ref "LED7") (pin "3-GND") (pinfunction "GND_3-GND") (pintype "bidirectional"))
      (node (ref "LED8") (pin "3-GND") (pinfunction "GND_3-GND") (pintype "bidirectional"))
      (node (ref "LED9") (pin "3-GND") (pinfunction "GND_3-GND") (pintype "bidirectional"))
      (node (ref "R7") (pin "P$2") (pinfunction "P$2_P$2") (pintype "passive"))
      (node (ref "SW1") (pin "1") (pinfunction "P_1") (pintype "passive"))
      (node (ref "SW2") (pin "1") (pinfunction "P_1") (pintype "passive"))
      (node (ref "U1") (pin "1") (pinfunction "ADJ_1") (pintype "input"))
      (node (ref "X1") (pin "9") (pinfunction "GND_9") (pintype "power_in"))
    )
    (net (code "12") (name "Net-(CN1-PWR)") (class "Default")
      (node (ref "CN1") (pin "PWR1") (pinfunction "PWR_PWR1") (pintype "power_in"))
      (node (ref "F1") (pin "2") (pinfunction "2_2") (pintype "passive"))
    )
    (net (code "13") (name "Net-(J1-CTS)") (class "Default")
      (node (ref "J1") (pin "5") (pinfunction "CTS_5") (pintype "bidirectional"))
      (node (ref "R6") (pin "P$1") (pinfunction "P$1_P$1") (pintype "passive"))
      (node (ref "U2") (pin "P$2") (pinfunction "SOURCE_P$2") (pintype "bidirectional"))
    )
    (net (code "14") (name "Net-(J1-DTR)") (class "Default")
      (node (ref "J1") (pin "1") (pinfunction "DTR_1") (pintype "bidirectional"))
      (node (ref "R1") (pin "P$1") (pinfunction "P$1_P$1") (pintype "passive"))
      (node (ref "U3") (pin "P$2") (pinfunction "SOURCE_P$2") (pintype "bidirectional"))
    )
    (net (code "15") (name "Net-(J1-RXI)") (class "Default")
      (node (ref "D1") (pin "C") (pinfunction "C_C") (pintype "passive"))
      (node (ref "J1") (pin "3") (pinfunction "RXI_3") (pintype "bidirectional"))
    )
    (net (code "16") (name "Net-(LED1-DIN)") (class "Default")
      (node (ref "LED1") (pin "4-DIN") (pinfunction "DIN_4-DIN") (pintype "input"))
      (node (ref "R10") (pin "P$1") (pinfunction "P$1_P$1") (pintype "passive"))
    )
    (net (code "17") (name "Net-(LED1-DOUT)") (class "Default")
      (node (ref "LED1") (pin "2-DOUT") (pinfunction "DOUT_2-DOUT") (pintype "output"))
      (node (ref "LED2") (pin "4-DIN") (pinfunction "DIN_4-DIN") (pintype "input"))
    )
    (net (code "18") (name "Net-(LED2-DOUT)") (class "Default")
      (node (ref "LED2") (pin "2-DOUT") (pinfunction "DOUT_2-DOUT") (pintype "output"))
      (node (ref "LED3") (pin "4-DIN") (pinfunction "DIN_4-DIN") (pintype "input"))
    )
    (net (code "19") (name "Net-(LED3-DOUT)") (class "Default")
      (node (ref "LED3") (pin "2-DOUT") (pinfunction "DOUT_2-DOUT") (pintype "output"))
      (node (ref "LED4") (pin "4-DIN") (pinfunction "DIN_4-DIN") (pintype "input"))
    )
    (net (code "20") (name "Net-(LED4-DOUT)") (class "Default")
      (node (ref "LED4") (pin "2-DOUT") (pinfunction "DOUT_2-DOUT") (pintype "output"))
      (node (ref "LED5") (pin "4-DIN") (pinfunction "DIN_4-DIN") (pintype "input"))
    )
    (net (code "21") (name "Net-(LED5-DOUT)") (class "Default")
      (node (ref "LED5") (pin "2-DOUT") (pinfunction "DOUT_2-DOUT") (pintype "output"))
      (node (ref "LED6") (pin "4-DIN") (pinfunction "DIN_4-DIN") (pintype "input"))
    )
    (net (code "22") (name "Net-(LED6-DOUT)") (class "Default")
      (node (ref "LED6") (pin "2-DOUT") (pinfunction "DOUT_2-DOUT") (pintype "output"))
      (node (ref "LED7") (pin "4-DIN") (pinfunction "DIN_4-DIN") (pintype "input"))
    )
    (net (code "23") (name "Net-(LED7-DOUT)") (class "Default")
      (node (ref "LED7") (pin "2-DOUT") (pinfunction "DOUT_2-DOUT") (pintype "output"))
      (node (ref "LED8") (pin "4-DIN") (pinfunction "DIN_4-DIN") (pintype "input"))
    )
    (net (code "24") (name "Net-(LED8-DOUT)") (class "Default")
      (node (ref "LED8") (pin "2-DOUT") (pinfunction "DOUT_2-DOUT") (pintype "output"))
      (node (ref "LED9") (pin "4-DIN") (pinfunction "DIN_4-DIN") (pintype "input"))
    )
    (net (code "25") (name "Net-(LED10-DIN)") (class "Default")
      (node (ref "LED10") (pin "4-DIN") (pinfunction "DIN_4-DIN") (pintype "input"))
      (node (ref "LED9") (pin "2-DOUT") (pinfunction "DOUT_2-DOUT") (pintype "output"))
    )
    (net (code "26") (name "Net-(LED10-DOUT)") (class "Default")
      (node (ref "LED10") (pin "2-DOUT") (pinfunction "DOUT_2-DOUT") (pintype "output"))
      (node (ref "LED11") (pin "4-DIN") (pinfunction "DIN_4-DIN") (pintype "input"))
    )
    (net (code "27") (name "Net-(LED11-DOUT)") (class "Default")
      (node (ref "LED11") (pin "2-DOUT") (pinfunction "DOUT_2-DOUT") (pintype "output"))
      (node (ref "LED12") (pin "4-DIN") (pinfunction "DIN_4-DIN") (pintype "input"))
    )
    (net (code "28") (name "Net-(LED12-DOUT)") (class "Default")
      (node (ref "LED12") (pin "2-DOUT") (pinfunction "DOUT_2-DOUT") (pintype "output"))
      (node (ref "LED13") (pin "4-DIN") (pinfunction "DIN_4-DIN") (pintype "input"))
    )
    (net (code "29") (name "Net-(LED13-DOUT)") (class "Default")
      (node (ref "LED13") (pin "2-DOUT") (pinfunction "DOUT_2-DOUT") (pintype "output"))
      (node (ref "LED14") (pin "4-DIN") (pinfunction "DIN_4-DIN") (pintype "input"))
    )
    (net (code "30") (name "Net-(LED14-DOUT)") (class "Default")
      (node (ref "LED14") (pin "2-DOUT") (pinfunction "DOUT_2-DOUT") (pintype "output"))
      (node (ref "LED15") (pin "4-DIN") (pinfunction "DIN_4-DIN") (pintype "input"))
    )
    (net (code "31") (name "Net-(LED15-DOUT)") (class "Default")
      (node (ref "LED15") (pin "2-DOUT") (pinfunction "DOUT_2-DOUT") (pintype "output"))
      (node (ref "LED16") (pin "4-DIN") (pinfunction "DIN_4-DIN") (pintype "input"))
    )
    (net (code "32") (name "Net-(LED16-DOUT)") (class "Default")
      (node (ref "LED16") (pin "2-DOUT") (pinfunction "DOUT_2-DOUT") (pintype "output"))
      (node (ref "LED17") (pin "4-DIN") (pinfunction "DIN_4-DIN") (pintype "input"))
    )
    (net (code "33") (name "Net-(LED17-DOUT)") (class "Default")
      (node (ref "LED17") (pin "2-DOUT") (pinfunction "DOUT_2-DOUT") (pintype "output"))
      (node (ref "LED18") (pin "4-DIN") (pinfunction "DIN_4-DIN") (pintype "input"))
    )
    (net (code "34") (name "Net-(LED18-DOUT)") (class "Default")
      (node (ref "LED18") (pin "2-DOUT") (pinfunction "DOUT_2-DOUT") (pintype "output"))
      (node (ref "LED19") (pin "4-DIN") (pinfunction "DIN_4-DIN") (pintype "input"))
    )
    (net (code "35") (name "Net-(LED19-DOUT)") (class "Default")
      (node (ref "LED19") (pin "2-DOUT") (pinfunction "DOUT_2-DOUT") (pintype "output"))
      (node (ref "LED20") (pin "4-DIN") (pinfunction "DIN_4-DIN") (pintype "input"))
    )
    (net (code "36") (name "Net-(LED20-DOUT)") (class "Default")
      (node (ref "LED20") (pin "2-DOUT") (pinfunction "DOUT_2-DOUT") (pintype "output"))
      (node (ref "LED21") (pin "4-DIN") (pinfunction "DIN_4-DIN") (pintype "input"))
    )
    (net (code "37") (name "Net-(LED21-DOUT)") (class "Default")
      (node (ref "LED21") (pin "2-DOUT") (pinfunction "DOUT_2-DOUT") (pintype "output"))
      (node (ref "LED22") (pin "4-DIN") (pinfunction "DIN_4-DIN") (pintype "input"))
    )
    (net (code "38") (name "Net-(LED22-DOUT)") (class "Default")
      (node (ref "LED22") (pin "2-DOUT") (pinfunction "DOUT_2-DOUT") (pintype "output"))
      (node (ref "LED23") (pin "4-DIN") (pinfunction "DIN_4-DIN") (pintype "input"))
    )
    (net (code "39") (name "Net-(LED23-DOUT)") (class "Default")
      (node (ref "LED23") (pin "2-DOUT") (pinfunction "DOUT_2-DOUT") (pintype "output"))
      (node (ref "LED24") (pin "4-DIN") (pinfunction "DIN_4-DIN") (pintype "input"))
    )
    (net (code "40") (name "Net-(LED24-DOUT)") (class "Default")
      (node (ref "LED24") (pin "2-DOUT") (pinfunction "DOUT_2-DOUT") (pintype "output"))
      (node (ref "LED25") (pin "4-DIN") (pinfunction "DIN_4-DIN") (pintype "input"))
    )
    (net (code "41") (name "Net-(LED25-DOUT)") (class "Default")
      (node (ref "LED25") (pin "2-DOUT") (pinfunction "DOUT_2-DOUT") (pintype "output"))
      (node (ref "LED26") (pin "4-DIN") (pinfunction "DIN_4-DIN") (pintype "input"))
    )
    (net (code "42") (name "Net-(LED26-DOUT)") (class "Default")
      (node (ref "LED26") (pin "2-DOUT") (pinfunction "DOUT_2-DOUT") (pintype "output"))
      (node (ref "LED27") (pin "4-DIN") (pinfunction "DIN_4-DIN") (pintype "input"))
    )
    (net (code "43") (name "Net-(LED27-DOUT)") (class "Default")
      (node (ref "LED27") (pin "2-DOUT") (pinfunction "DOUT_2-DOUT") (pintype "output"))
      (node (ref "LED28") (pin "4-DIN") (pinfunction "DIN_4-DIN") (pintype "input"))
    )
    (net (code "44") (name "Net-(LED28-DOUT)") (class "Default")
      (node (ref "LED28") (pin "2-DOUT") (pinfunction "DOUT_2-DOUT") (pintype "output"))
      (node (ref "LED29") (pin "4-DIN") (pinfunction "DIN_4-DIN") (pintype "input"))
    )
    (net (code "45") (name "Net-(LED29-DOUT)") (class "Default")
      (node (ref "LED29") (pin "2-DOUT") (pinfunction "DOUT_2-DOUT") (pintype "output"))
      (node (ref "LED30") (pin "4-DIN") (pinfunction "DIN_4-DIN") (pintype "input"))
    )
    (net (code "46") (name "Net-(LED30-DOUT)") (class "Default")
      (node (ref "LED30") (pin "2-DOUT") (pinfunction "DOUT_2-DOUT") (pintype "output"))
      (node (ref "LED31") (pin "4-DIN") (pinfunction "DIN_4-DIN") (pintype "input"))
    )
    (net (code "47") (name "Net-(LED31-DOUT)") (class "Default")
      (node (ref "LED31") (pin "2-DOUT") (pinfunction "DOUT_2-DOUT") (pintype "output"))
      (node (ref "LED32") (pin "4-DIN") (pinfunction "DIN_4-DIN") (pintype "input"))
    )
    (net (code "48") (name "Net-(LED32-DOUT)") (class "Default")
      (node (ref "LED32") (pin "2-DOUT") (pinfunction "DOUT_2-DOUT") (pintype "output"))
      (node (ref "LED33") (pin "4-DIN") (pinfunction "DIN_4-DIN") (pintype "input"))
    )
    (net (code "49") (name "Net-(LED33-DOUT)") (class "Default")
      (node (ref "LED33") (pin "2-DOUT") (pinfunction "DOUT_2-DOUT") (pintype "output"))
      (node (ref "LED34") (pin "4-DIN") (pinfunction "DIN_4-DIN") (pintype "input"))
    )
    (net (code "50") (name "Net-(LED34-DOUT)") (class "Default")
      (node (ref "LED34") (pin "2-DOUT") (pinfunction "DOUT_2-DOUT") (pintype "output"))
      (node (ref "LED35") (pin "4-DIN") (pinfunction "DIN_4-DIN") (pintype "input"))
    )
    (net (code "51") (name "Net-(LED35-DOUT)") (class "Default")
      (node (ref "LED35") (pin "2-DOUT") (pinfunction "DOUT_2-DOUT") (pintype "output"))
      (node (ref "LED36") (pin "4-DIN") (pinfunction "DIN_4-DIN") (pintype "input"))
    )
    (net (code "52") (name "Net-(LED36-DOUT)") (class "Default")
      (node (ref "LED36") (pin "2-DOUT") (pinfunction "DOUT_2-DOUT") (pintype "output"))
      (node (ref "LED37") (pin "4-DIN") (pinfunction "DIN_4-DIN") (pintype "input"))
    )
    (net (code "53") (name "Net-(LED37-DOUT)") (class "Default")
      (node (ref "LED37") (pin "2-DOUT") (pinfunction "DOUT_2-DOUT") (pintype "output"))
      (node (ref "LED38") (pin "4-DIN") (pinfunction "DIN_4-DIN") (pintype "input"))
    )
    (net (code "54") (name "Net-(LED38-DOUT)") (class "Default")
      (node (ref "LED38") (pin "2-DOUT") (pinfunction "DOUT_2-DOUT") (pintype "output"))
      (node (ref "LED39") (pin "4-DIN") (pinfunction "DIN_4-DIN") (pintype "input"))
    )
    (net (code "55") (name "Net-(LED39-DOUT)") (class "Default")
      (node (ref "LED39") (pin "2-DOUT") (pinfunction "DOUT_2-DOUT") (pintype "output"))
      (node (ref "LED40") (pin "4-DIN") (pinfunction "DIN_4-DIN") (pintype "input"))
    )
    (net (code "56") (name "Net-(LED40-DOUT)") (class "Default")
      (node (ref "LED40") (pin "2-DOUT") (pinfunction "DOUT_2-DOUT") (pintype "output"))
      (node (ref "LED41") (pin "4-DIN") (pinfunction "DIN_4-DIN") (pintype "input"))
    )
    (net (code "57") (name "Net-(LED41-DOUT)") (class "Default")
      (node (ref "LED41") (pin "2-DOUT") (pinfunction "DOUT_2-DOUT") (pintype "output"))
      (node (ref "LED42") (pin "4-DIN") (pinfunction "DIN_4-DIN") (pintype "input"))
    )
    (net (code "58") (name "Net-(LED42-DOUT)") (class "Default")
      (node (ref "LED42") (pin "2-DOUT") (pinfunction "DOUT_2-DOUT") (pintype "output"))
      (node (ref "LED43") (pin "4-DIN") (pinfunction "DIN_4-DIN") (pintype "input"))
    )
    (net (code "59") (name "Net-(LED43-DOUT)") (class "Default")
      (node (ref "LED43") (pin "2-DOUT") (pinfunction "DOUT_2-DOUT") (pintype "output"))
      (node (ref "LED44") (pin "4-DIN") (pinfunction "DIN_4-DIN") (pintype "input"))
    )
    (net (code "60") (name "Net-(LED44-DOUT)") (class "Default")
      (node (ref "LED44") (pin "2-DOUT") (pinfunction "DOUT_2-DOUT") (pintype "output"))
      (node (ref "LED45") (pin "4-DIN") (pinfunction "DIN_4-DIN") (pintype "input"))
    )
    (net (code "61") (name "Net-(LED45-DOUT)") (class "Default")
      (node (ref "LED45") (pin "2-DOUT") (pinfunction "DOUT_2-DOUT") (pintype "output"))
      (node (ref "LED46") (pin "4-DIN") (pinfunction "DIN_4-DIN") (pintype "input"))
    )
    (net (code "62") (name "Net-(LED46-DOUT)") (class "Default")
      (node (ref "LED46") (pin "2-DOUT") (pinfunction "DOUT_2-DOUT") (pintype "output"))
      (node (ref "LED47") (pin "4-DIN") (pinfunction "DIN_4-DIN") (pintype "input"))
    )
    (net (code "63") (name "Net-(LED47-DOUT)") (class "Default")
      (node (ref "LED47") (pin "2-DOUT") (pinfunction "DOUT_2-DOUT") (pintype "output"))
      (node (ref "LED48") (pin "4-DIN") (pinfunction "DIN_4-DIN") (pintype "input"))
    )
    (net (code "64") (name "Net-(LED48-DOUT)") (class "Default")
      (node (ref "LED48") (pin "2-DOUT") (pinfunction "DOUT_2-DOUT") (pintype "output"))
      (node (ref "LED49") (pin "4-DIN") (pinfunction "DIN_4-DIN") (pintype "input"))
    )
    (net (code "65") (name "Net-(LED49-DOUT)") (class "Default")
      (node (ref "LED49") (pin "2-DOUT") (pinfunction "DOUT_2-DOUT") (pintype "output"))
      (node (ref "LED50") (pin "4-DIN") (pinfunction "DIN_4-DIN") (pintype "input"))
    )
    (net (code "66") (name "Net-(LED50-DOUT)") (class "Default")
      (node (ref "LED50") (pin "2-DOUT") (pinfunction "DOUT_2-DOUT") (pintype "output"))
      (node (ref "LED51") (pin "4-DIN") (pinfunction "DIN_4-DIN") (pintype "input"))
    )
    (net (code "67") (name "Net-(LED51-DOUT)") (class "Default")
      (node (ref "LED51") (pin "2-DOUT") (pinfunction "DOUT_2-DOUT") (pintype "output"))
      (node (ref "LED52") (pin "4-DIN") (pinfunction "DIN_4-DIN") (pintype "input"))
    )
    (net (code "68") (name "Net-(LED52-DOUT)") (class "Default")
      (node (ref "LED52") (pin "2-DOUT") (pinfunction "DOUT_2-DOUT") (pintype "output"))
      (node (ref "LED53") (pin "4-DIN") (pinfunction "DIN_4-DIN") (pintype "input"))
    )
    (net (code "69") (name "Net-(LED53-DOUT)") (class "Default")
      (node (ref "LED53") (pin "2-DOUT") (pinfunction "DOUT_2-DOUT") (pintype "output"))
      (node (ref "LED54") (pin "4-DIN") (pinfunction "DIN_4-DIN") (pintype "input"))
    )
    (net (code "70") (name "Net-(LED54-DOUT)") (class "Default")
      (node (ref "LED54") (pin "2-DOUT") (pinfunction "DOUT_2-DOUT") (pintype "output"))
      (node (ref "LED55") (pin "4-DIN") (pinfunction "DIN_4-DIN") (pintype "input"))
    )
    (net (code "71") (name "Net-(LED55-DOUT)") (class "Default")
      (node (ref "LED55") (pin "2-DOUT") (pinfunction "DOUT_2-DOUT") (pintype "output"))
      (node (ref "LED56") (pin "4-DIN") (pinfunction "DIN_4-DIN") (pintype "input"))
    )
    (net (code "72") (name "Net-(LED56-DOUT)") (class "Default")
      (node (ref "LED56") (pin "2-DOUT") (pinfunction "DOUT_2-DOUT") (pintype "output"))
      (node (ref "LED57") (pin "4-DIN") (pinfunction "DIN_4-DIN") (pintype "input"))
    )
    (net (code "73") (name "Net-(LED57-DOUT)") (class "Default")
      (node (ref "LED57") (pin "2-DOUT") (pinfunction "DOUT_2-DOUT") (pintype "output"))
      (node (ref "LED58") (pin "4-DIN") (pinfunction "DIN_4-DIN") (pintype "input"))
    )
    (net (code "74") (name "Net-(LED58-DOUT)") (class "Default")
      (node (ref "LED58") (pin "2-DOUT") (pinfunction "DOUT_2-DOUT") (pintype "output"))
      (node (ref "LED59") (pin "4-DIN") (pinfunction "DIN_4-DIN") (pintype "input"))
    )
    (net (code "75") (name "Net-(LED59-DOUT)") (class "Default")
      (node (ref "LED59") (pin "2-DOUT") (pinfunction "DOUT_2-DOUT") (pintype "output"))
      (node (ref "LED60") (pin "4-DIN") (pinfunction "DIN_4-DIN") (pintype "input"))
    )
    (net (code "76") (name "Net-(LED60-DOUT)") (class "Default")
      (node (ref "LED60") (pin "2-DOUT") (pinfunction "DOUT_2-DOUT") (pintype "output"))
      (node (ref "LED61") (pin "4-DIN") (pinfunction "DIN_4-DIN") (pintype "input"))
    )
    (net (code "77") (name "Net-(LED61-DOUT)") (class "Default")
      (node (ref "LED61") (pin "2-DOUT") (pinfunction "DOUT_2-DOUT") (pintype "output"))
      (node (ref "LED62") (pin "4-DIN") (pinfunction "DIN_4-DIN") (pintype "input"))
    )
    (net (code "78") (name "Net-(LED62-DOUT)") (class "Default")
      (node (ref "LED62") (pin "2-DOUT") (pinfunction "DOUT_2-DOUT") (pintype "output"))
      (node (ref "LED63") (pin "4-DIN") (pinfunction "DIN_4-DIN") (pintype "input"))
    )
    (net (code "79") (name "Net-(LED63-DOUT)") (class "Default")
      (node (ref "LED63") (pin "2-DOUT") (pinfunction "DOUT_2-DOUT") (pintype "output"))
      (node (ref "LED64") (pin "4-DIN") (pinfunction "DIN_4-DIN") (pintype "input"))
    )
    (net (code "80") (name "Net-(U2-GATE)") (class "Default")
      (node (ref "R1") (pin "P$2") (pinfunction "P$2_P$2") (pintype "passive"))
      (node (ref "U2") (pin "P$1") (pinfunction "GATE_P$1") (pintype "bidirectional"))
    )
    (net (code "81") (name "Net-(U3-GATE)") (class "Default")
      (node (ref "R6") (pin "P$2") (pinfunction "P$2_P$2") (pintype "passive"))
      (node (ref "U3") (pin "P$1") (pinfunction "GATE_P$1") (pintype "bidirectional"))
    )
    (net (code "82") (name "Net-(U4-DRAIN)") (class "Default")
      (node (ref "R10") (pin "P$2") (pinfunction "P$2_P$2") (pintype "passive"))
      (node (ref "R8") (pin "P$1") (pinfunction "P$1_P$1") (pintype "passive"))
      (node (ref "U4") (pin "P$3") (pinfunction "DRAIN_P$3") (pintype "bidirectional"))
    )
    (net (code "83") (name "Net-(X1-CH_PD)") (class "Default")
      (node (ref "R2") (pin "P$2") (pinfunction "P$2_P$2") (pintype "passive"))
      (node (ref "X1") (pin "3") (pinfunction "CH_PD_3") (pintype "input"))
    )
    (net (code "84") (name "Net-(X1-GPIO2)") (class "Default")
      (node (ref "R5") (pin "P$2") (pinfunction "P$2_P$2") (pintype "passive"))
      (node (ref "X1") (pin "11") (pinfunction "GPIO2_11") (pintype "bidirectional"))
    )
    (net (code "85") (name "VCC") (class "Default")
      (node (ref "C1") (pin "A") (pinfunction "+_A") (pintype "passive"))
      (node (ref "C10") (pin "2") (pinfunction "2_2") (pintype "passive"))
      (node (ref "C11") (pin "2") (pinfunction "2_2") (pintype "passive"))
      (node (ref "C12") (pin "2") (pinfunction "2_2") (pintype "passive"))
      (node (ref "C13") (pin "2") (pinfunction "2_2") (pintype "passive"))
      (node (ref "C14") (pin "2") (pinfunction "2_2") (pintype "passive"))
      (node (ref "C15") (pin "2") (pinfunction "2_2") (pintype "passive"))
      (node (ref "C16") (pin "2") (pinfunction "2_2") (pintype "passive"))
      (node (ref "C17") (pin "2") (pinfunction "2_2") (pintype "passive"))
      (node (ref "C18") (pin "2") (pinfunction "2_2") (pintype "passive"))
      (node (ref "C19") (pin "2") (pinfunction "2_2") (pintype "passive"))
      (node (ref "C20") (pin "2") (pinfunction "2_2") (pintype "passive"))
      (node (ref "C21") (pin "2") (pinfunction "2_2") (pintype "passive"))
      (node (ref "C22") (pin "2") (pinfunction "2_2") (pintype "passive"))
      (node (ref "C23") (pin "2") (pinfunction "2_2") (pintype "passive"))
      (node (ref "C24") (pin "2") (pinfunction "2_2") (pintype "passive"))
      (node (ref "C25") (pin "2") (pinfunction "2_2") (pintype "passive"))
      (node (ref "C26") (pin "2") (pinfunction "2_2") (pintype "passive"))
      (node (ref "C27") (pin "2") (pinfunction "2_2") (pintype "passive"))
      (node (ref "C28") (pin "2") (pinfunction "2_2") (pintype "passive"))
      (node (ref "C29") (pin "2") (pinfunction "2_2") (pintype "passive"))
      (node (ref "C30") (pin "2") (pinfunction "2_2") (pintype "passive"))
      (node (ref "C31") (pin "2") (pinfunction "2_2") (pintype "passive"))
      (node (ref "C32") (pin "2") (pinfunction "2_2") (pintype "passive"))
      (node (ref "C33") (pin "2") (pinfunction "2_2") (pintype "passive"))
      (node (ref "C34") (pin "2") (pinfunction "2_2") (pintype "passive"))
      (node (ref "C35") (pin "2") (pinfunction "2_2") (pintype "passive"))
      (node (ref "C36") (pin "2") (pinfunction "2_2") (pintype "passive"))
      (node (ref "C37") (pin "2") (pinfunction "2_2") (pintype "passive"))
      (node (ref "C38") (pin "2") (pinfunction "2_2") (pintype "passive"))
      (node (ref "C39") (pin "2") (pinfunction "2_2") (pintype "passive"))
      (node (ref "C4") (pin "2") (pinfunction "2_2") (pintype "passive"))
      (node (ref "C40") (pin "2") (pinfunction "2_2") (pintype "passive"))
      (node (ref "C41") (pin "2") (pinfunction "2_2") (pintype "passive"))
      (node (ref "C42") (pin "2") (pinfunction "2_2") (pintype "passive"))
      (node (ref "C43") (pin "2") (pinfunction "2_2") (pintype "passive"))
      (node (ref "C44") (pin "2") (pinfunction "2_2") (pintype "passive"))
      (node (ref "C45") (pin "2") (pinfunction "2_2") (pintype "passive"))
      (node (ref "C46") (pin "2") (pinfunction "2_2") (pintype "passive"))
      (node (ref "C47") (pin "2") (pinfunction "2_2") (pintype "passive"))
      (node (ref "C48") (pin "2") (pinfunction "2_2") (pintype "passive"))
      (node (ref "C49") (pin "2") (pinfunction "2_2") (pintype "passive"))
      (node (ref "C5") (pin "2") (pinfunction "2_2") (pintype "passive"))
      (node (ref "C50") (pin "2") (pinfunction "2_2") (pintype "passive"))
      (node (ref "C51") (pin "2") (pinfunction "2_2") (pintype "passive"))
      (node (ref "C52") (pin "2") (pinfunction "2_2") (pintype "passive"))
      (node (ref "C53") (pin "2") (pinfunction "2_2") (pintype "passive"))
      (node (ref "C54") (pin "2") (pinfunction "2_2") (pintype "passive"))
      (node (ref "C55") (pin "2") (pinfunction "2_2") (pintype "passive"))
      (node (ref "C56") (pin "2") (pinfunction "2_2") (pintype "passive"))
      (node (ref "C57") (pin "2") (pinfunction "2_2") (pintype "passive"))
      (node (ref "C58") (pin "2") (pinfunction "2_2") (pintype "passive"))
      (node (ref "C59") (pin "2") (pinfunction "2_2") (pintype "passive"))
      (node (ref "C6") (pin "2") (pinfunction "2_2") (pintype "passive"))
      (node (ref "C60") (pin "2") (pinfunction "2_2") (pintype "passive"))
      (node (ref "C61") (pin "2") (pinfunction "2_2") (pintype "passive"))
      (node (ref "C62") (pin "2") (pinfunction "2_2") (pintype "passive"))
      (node (ref "C63") (pin "2") (pinfunction "2_2") (pintype "passive"))
      (node (ref "C64") (pin "2") (pinfunction "2_2") (pintype "passive"))
      (node (ref "C65") (pin "2") (pinfunction "2_2") (pintype "passive"))
      (node (ref "C66") (pin "2") (pinfunction "2_2") (pintype "passive"))
      (node (ref "C7") (pin "2") (pinfunction "2_2") (pintype "passive"))
      (node (ref "C8") (pin "2") (pinfunction "2_2") (pintype "passive"))
      (node (ref "C9") (pin "2") (pinfunction "2_2") (pintype "passive"))
      (node (ref "F1") (pin "1") (pinfunction "1_1") (pintype "passive"))
      (node (ref "LED1") (pin "1-VDD") (pinfunction "VDD_1-VDD") (pintype "bidirectional"))
      (node (ref "LED10") (pin "1-VDD") (pinfunction "VDD_1-VDD") (pintype "bidirectional"))
      (node (ref "LED11") (pin "1-VDD") (pinfunction "VDD_1-VDD") (pintype "bidirectional"))
      (node (ref "LED12") (pin "1-VDD") (pinfunction "VDD_1-VDD") (pintype "bidirectional"))
      (node (ref "LED13") (pin "1-VDD") (pinfunction "VDD_1-VDD") (pintype "bidirectional"))
      (node (ref "LED14") (pin "1-VDD") (pinfunction "VDD_1-VDD") (pintype "bidirectional"))
      (node (ref "LED15") (pin "1-VDD") (pinfunction "VDD_1-VDD") (pintype "bidirectional"))
      (node (ref "LED16") (pin "1-VDD") (pinfunction "VDD_1-VDD") (pintype "bidirectional"))
      (node (ref "LED17") (pin "1-VDD") (pinfunction "VDD_1-VDD") (pintype "bidirectional"))
      (node (ref "LED18") (pin "1-VDD") (pinfunction "VDD_1-VDD") (pintype "bidirectional"))
      (node (ref "LED19") (pin "1-VDD") (pinfunction "VDD_1-VDD") (pintype "bidirectional"))
      (node (ref "LED2") (pin "1-VDD") (pinfunction "VDD_1-VDD") (pintype "bidirectional"))
      (node (ref "LED20") (pin "1-VDD") (pinfunction "VDD_1-VDD") (pintype "bidirectional"))
      (node (ref "LED21") (pin "1-VDD") (pinfunction "VDD_1-VDD") (pintype "bidirectional"))
      (node (ref "LED22") (pin "1-VDD") (pinfunction "VDD_1-VDD") (pintype "bidirectional"))
      (node (ref "LED23") (pin "1-VDD") (pinfunction "VDD_1-VDD") (pintype "bidirectional"))
      (node (ref "LED24") (pin "1-VDD") (pinfunction "VDD_1-VDD") (pintype "bidirectional"))
      (node (ref "LED25") (pin "1-VDD") (pinfunction "VDD_1-VDD") (pintype "bidirectional"))
      (node (ref "LED26") (pin "1-VDD") (pinfunction "VDD_1-VDD") (pintype "bidirectional"))
      (node (ref "LED27") (pin "1-VDD") (pinfunction "VDD_1-VDD") (pintype "bidirectional"))
      (node (ref "LED28") (pin "1-VDD") (pinfunction "VDD_1-VDD") (pintype "bidirectional"))
      (node (ref "LED29") (pin "1-VDD") (pinfunction "VDD_1-VDD") (pintype "bidirectional"))
      (node (ref "LED3") (pin "1-VDD") (pinfunction "VDD_1-VDD") (pintype "bidirectional"))
      (node (ref "LED30") (pin "1-VDD") (pinfunction "VDD_1-VDD") (pintype "bidirectional"))
      (node (ref "LED31") (pin "1-VDD") (pinfunction "VDD_1-VDD") (pintype "bidirectional"))
      (node (ref "LED32") (pin "1-VDD") (pinfunction "VDD_1-VDD") (pintype "bidirectional"))
      (node (ref "LED33") (pin "1-VDD") (pinfunction "VDD_1-VDD") (pintype "bidirectional"))
      (node (ref "LED34") (pin "1-VDD") (pinfunction "VDD_1-VDD") (pintype "bidirectional"))
      (node (ref "LED35") (pin "1-VDD") (pinfunction "VDD_1-VDD") (pintype "bidirectional"))
      (node (ref "LED36") (pin "1-VDD") (pinfunction "VDD_1-VDD") (pintype "bidirectional"))
      (node (ref "LED37") (pin "1-VDD") (pinfunction "VDD_1-VDD") (pintype "bidirectional"))
      (node (ref "LED38") (pin "1-VDD") (pinfunction "VDD_1-VDD") (pintype "bidirectional"))
      (node (ref "LED39") (pin "1-VDD") (pinfunction "VDD_1-VDD") (pintype "bidirectional"))
      (node (ref "LED4") (pin "1-VDD") (pinfunction "VDD_1-VDD") (pintype "bidirectional"))
      (node (ref "LED40") (pin "1-VDD") (pinfunction "VDD_1-VDD") (pintype "bidirectional"))
      (node (ref "LED41") (pin "1-VDD") (pinfunction "VDD_1-VDD") (pintype "bidirectional"))
      (node (ref "LED42") (pin "1-VDD") (pinfunction "VDD_1-VDD") (pintype "bidirectional"))
      (node (ref "LED43") (pin "1-VDD") (pinfunction "VDD_1-VDD") (pintype "bidirectional"))
      (node (ref "LED44") (pin "1-VDD") (pinfunction "VDD_1-VDD") (pintype "bidirectional"))
      (node (ref "LED45") (pin "1-VDD") (pinfunction "VDD_1-VDD") (pintype "bidirectional"))
      (node (ref "LED46") (pin "1-VDD") (pinfunction "VDD_1-VDD") (pintype "bidirectional"))
      (node (ref "LED47") (pin "1-VDD") (pinfunction "VDD_1-VDD") (pintype "bidirectional"))
      (node (ref "LED48") (pin "1-VDD") (pinfunction "VDD_1-VDD") (pintype "bidirectional"))
      (node (ref "LED49") (pin "1-VDD") (pinfunction "VDD_1-VDD") (pintype "bidirectional"))
      (node (ref "LED5") (pin "1-VDD") (pinfunction "VDD_1-VDD") (pintype "bidirectional"))
      (node (ref "LED50") (pin "1-VDD") (pinfunction "VDD_1-VDD") (pintype "bidirectional"))
      (node (ref "LED51") (pin "1-VDD") (pinfunction "VDD_1-VDD") (pintype "bidirectional"))
      (node (ref "LED52") (pin "1-VDD") (pinfunction "VDD_1-VDD") (pintype "bidirectional"))
      (node (ref "LED53") (pin "1-VDD") (pinfunction "VDD_1-VDD") (pintype "bidirectional"))
      (node (ref "LED54") (pin "1-VDD") (pinfunction "VDD_1-VDD") (pintype "bidirectional"))
      (node (ref "LED55") (pin "1-VDD") (pinfunction "VDD_1-VDD") (pintype "bidirectional"))
      (node (ref "LED56") (pin "1-VDD") (pinfunction "VDD_1-VDD") (pintype "bidirectional"))
      (node (ref "LED57") (pin "1-VDD") (pinfunction "VDD_1-VDD") (pintype "bidirectional"))
      (node (ref "LED58") (pin "1-VDD") (pinfunction "VDD_1-VDD") (pintype "bidirectional"))
      (node (ref "LED59") (pin "1-VDD") (pinfunction "VDD_1-VDD") (pintype "bidirectional"))
      (node (ref "LED6") (pin "1-VDD") (pinfunction "VDD_1-VDD") (pintype "bidirectional"))
      (node (ref "LED60") (pin "1-VDD") (pinfunction "VDD_1-VDD") (pintype "bidirectional"))
      (node (ref "LED61") (pin "1-VDD") (pinfunction "VDD_1-VDD") (pintype "bidirectional"))
      (node (ref "LED62") (pin "1-VDD") (pinfunction "VDD_1-VDD") (pintype "bidirectional"))
      (node (ref "LED63") (pin "1-VDD") (pinfunction "VDD_1-VDD") (pintype "bidirectional"))
      (node (ref "LED64") (pin "1-VDD") (pinfunction "VDD_1-VDD") (pintype "bidirectional"))
      (node (ref "LED7") (pin "1-VDD") (pinfunction "VDD_1-VDD") (pintype "bidirectional"))
      (node (ref "LED8") (pin "1-VDD") (pinfunction "VDD_1-VDD") (pintype "bidirectional"))
      (node (ref "LED9") (pin "1-VDD") (pinfunction "VDD_1-VDD") (pintype "bidirectional"))
      (node (ref "R8") (pin "P$2") (pinfunction "P$2_P$2") (pintype "passive"))
      (node (ref "U1") (pin "3") (pinfunction "IN_3") (pintype "input"))
    )
    (net (code "86") (name "unconnected-(LED64-DOUT-Pad2-DOUT)") (class "Default")
      (node (ref "LED64") (pin "2-DOUT") (pinfunction "DOUT_2-DOUT") (pintype "output"))
    )
    (net (code "87") (name "unconnected-(SW1-P1-Pad3)") (class "Default")
      (node (ref "SW1") (pin "3") (pinfunction "P1_3") (pintype "passive"))
    )
    (net (code "88") (name "unconnected-(SW1-S1-Pad4)") (class "Default")
      (node (ref "SW1") (pin "4") (pinfunction "S1_4") (pintype "passive"))
    )
    (net (code "89") (name "unconnected-(SW2-P1-Pad3)") (class "Default")
      (node (ref "SW2") (pin "3") (pinfunction "P1_3") (pintype "passive"))
    )
    (net (code "90") (name "unconnected-(SW2-S1-Pad4)") (class "Default")
      (node (ref "SW2") (pin "4") (pinfunction "S1_4") (pintype "passive"))
    )
    (net (code "91") (name "unconnected-(X1-ADC-Pad2)") (class "Default")
      (node (ref "X1") (pin "2") (pinfunction "ADC_2") (pintype "passive"))
    )
    (net (code "92") (name "unconnected-(X1-GPIO4-Pad13)") (class "Default")
      (node (ref "X1") (pin "13") (pinfunction "GPIO4_13") (pintype "bidirectional"))
    )
  )
)
